# ESP.net
KiCad netlist of a schematic drawn in EAGLE
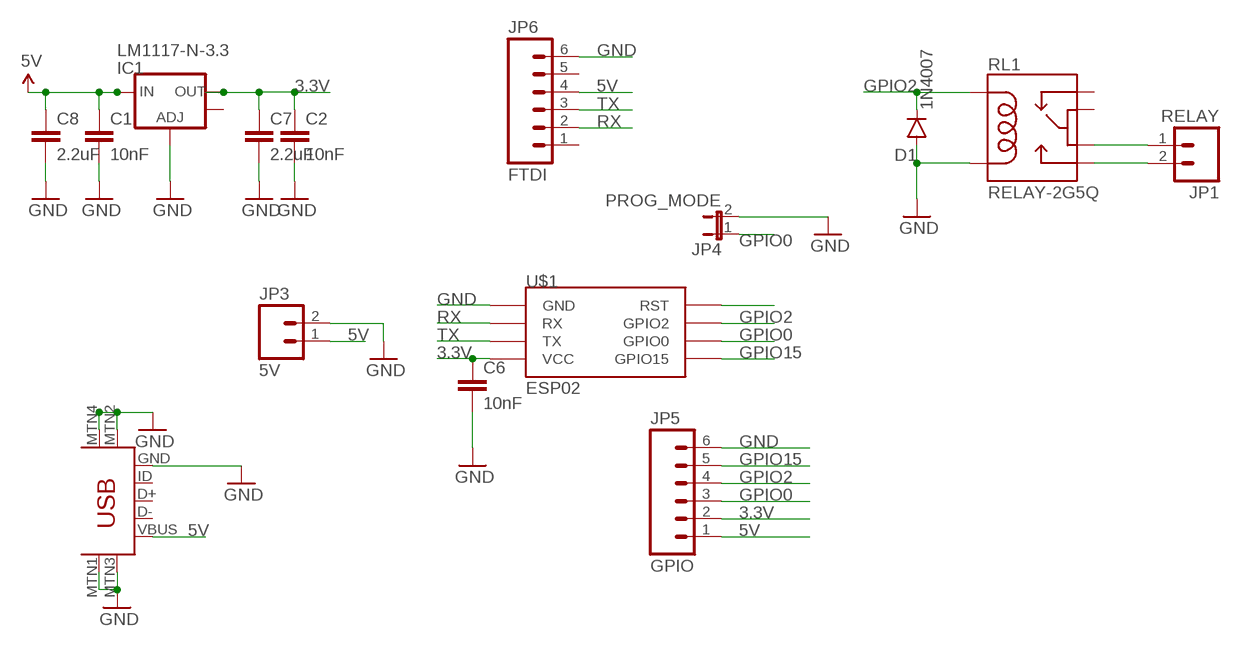
[diagram p0: schematic, sheet 1]

(export (version "E")
  (design (tool "Eeschema 10.0.6"))
  (components
    (comp (ref "C1")
      (value "10nF")
      (footprint "eagle-import:0603-CAP")
      (libsource (lib "eagle-import") (part "10NF/10000PF-50V-10%(0603)"))
    )
    (comp (ref "C2")
      (value "10nF")
      (footprint "eagle-import:0603-CAP")
      (libsource (lib "eagle-import") (part "10NF/10000PF-50V-10%(0603)"))
    )
    (comp (ref "C6")
      (value "10nF")
      (footprint "eagle-import:0603-CAP")
      (libsource (lib "eagle-import") (part "10NF/10000PF-50V-10%(0603)"))
    )
    (comp (ref "C7")
      (value "2.2uF")
      (footprint "eagle-import:0805")
      (libsource (lib "eagle-import") (part "2.2UF-25V-+80/-20(0805)"))
    )
    (comp (ref "C8")
      (value "2.2uF")
      (footprint "eagle-import:0805")
      (libsource (lib "eagle-import") (part "2.2UF-25V-+80/-20(0805)"))
    )
    (comp (ref "D1")
      (value "1N4007")
      (footprint "eagle-import:SMB-DIODE")
      (libsource (lib "eagle-import") (part "DIODESMB"))
    )
    (comp (ref "IC1")
      (value "LM1117-N-3.3")
      (footprint "eagle-import:SOT223")
      (libsource (lib "eagle-import") (part "V_REG_LM1117SOT223"))
    )
    (comp (ref "JP1")
      (value "RELAY")
      (footprint "eagle-import:SCREWTERMINAL-5MM-2")
      (libsource (lib "eagle-import") (part "M025MM"))
    )
    (comp (ref "JP3")
      (value "5V")
      (footprint "eagle-import:SCREWTERMINAL-5MM-2")
      (libsource (lib "eagle-import") (part "M025MM"))
    )
    (comp (ref "JP4")
      (value "PROG_MODE")
      (footprint "eagle-import:1X02")
      (libsource (lib "eagle-import") (part "JUMPER-2PTH"))
    )
    (comp (ref "JP5")
      (value "GPIO")
      (footprint "eagle-import:1X06")
      (libsource (lib "eagle-import") (part "M06SILK_FEMALE_PTH"))
    )
    (comp (ref "JP6")
      (value "FTDI")
      (footprint "eagle-import:1X06")
      (libsource (lib "eagle-import") (part "M06SILK_FEMALE_PTH"))
    )
    (comp (ref "RL1")
      (value "RELAY-2G5Q")
      (footprint "eagle-import:RELAY-G5V")
      (libsource (lib "eagle-import") (part "RELAY-2G5Q"))
    )
    (comp (ref "U$1")
      (value "ESP02")
      (footprint "eagle-import:ESP02")
      (libsource (lib "eagle-import") (part "ESP02"))
    )
    (comp (ref "U$2")
      (value "USB")
      (footprint "eagle-import:USB-MINIB")
      (libsource (lib "eagle-import") (part "USB-MINIB-5PIN"))
    )
  )
  (nets
    (net (code "1") (name "/3.3V") (class "Default")
      (node (ref "C2") (pin "1") (pinfunction "1_1") (pintype "passive"))
      (node (ref "C6") (pin "1") (pinfunction "1_1") (pintype "passive"))
      (node (ref "C7") (pin "1") (pinfunction "1_1") (pintype "passive"))
      (node (ref "IC1") (pin "2") (pinfunction "OUT_2") (pintype "output"))
      (node (ref "JP5") (pin "2") (pinfunction "2_2") (pintype "passive"))
      (node (ref "U$1") (pin "VCC") (pinfunction "VCC_VCC") (pintype "bidirectional"))
    )
    (net (code "2") (name "/GPIO0") (class "Default")
      (node (ref "JP4") (pin "1") (pinfunction "1_1") (pintype "passive"))
      (node (ref "JP5") (pin "3") (pinfunction "3_3") (pintype "passive"))
      (node (ref "U$1") (pin "GPIO0") (pinfunction "GPIO0_GPIO0") (pintype "bidirectional"))
    )
    (net (code "3") (name "/GPIO2") (class "Default")
      (node (ref "D1") (pin "C") (pinfunction "C_C") (pintype "passive"))
      (node (ref "JP5") (pin "4") (pinfunction "4_4") (pintype "passive"))
      (node (ref "RL1") (pin "2") (pinfunction "2_2") (pintype "bidirectional"))
      (node (ref "U$1") (pin "GPIO2") (pinfunction "GPIO2_GPIO2") (pintype "bidirectional"))
    )
    (net (code "4") (name "/GPIO15") (class "Default")
      (node (ref "JP5") (pin "5") (pinfunction "5_5") (pintype "passive"))
      (node (ref "U$1") (pin "GPIO15/POWERDOWN") (pinfunction "GPIO15_GPIO15/POWERDOWN") (pintype "bidirectional"))
    )
    (net (code "5") (name "/RX") (class "Default")
      (node (ref "JP6") (pin "2") (pinfunction "2_2") (pintype "passive"))
      (node (ref "U$1") (pin "RX") (pinfunction "RX_RX") (pintype "bidirectional"))
    )
    (net (code "6") (name "/TX") (class "Default")
      (node (ref "JP6") (pin "3") (pinfunction "3_3") (pintype "passive"))
      (node (ref "U$1") (pin "TX") (pinfunction "TX_TX") (pintype "bidirectional"))
    )
    (net (code "7") (name "5V") (class "Default")
      (node (ref "C1") (pin "1") (pinfunction "1_1") (pintype "passive"))
      (node (ref "C8") (pin "1") (pinfunction "1_1") (pintype "passive"))
      (node (ref "IC1") (pin "3") (pinfunction "IN_3") (pintype "input"))
      (node (ref "JP3") (pin "1") (pinfunction "1_1") (pintype "passive"))
      (node (ref "JP5") (pin "1") (pinfunction "1_1") (pintype "passive"))
      (node (ref "JP6") (pin "4") (pinfunction "4_4") (pintype "passive"))
      (node (ref "U$2") (pin "VBUS") (pinfunction "VBUS_VBUS") (pintype "bidirectional"))
    )
    (net (code "8") (name "GND") (class "Default")
      (node (ref "C1") (pin "2") (pinfunction "2_2") (pintype "passive"))
      (node (ref "C2") (pin "2") (pinfunction "2_2") (pintype "passive"))
      (node (ref "C6") (pin "2") (pinfunction "2_2") (pintype "passive"))
      (node (ref "C7") (pin "2") (pinfunction "2_2") (pintype "passive"))
      (node (ref "C8") (pin "2") (pinfunction "2_2") (pintype "passive"))
      (node (ref "D1") (pin "A") (pinfunction "A_A") (pintype "passive"))
      (node (ref "IC1") (pin "1") (pinfunction "ADJ_1") (pintype "input"))
      (node (ref "JP3") (pin "2") (pinfunction "2_2") (pintype "passive"))
      (node (ref "JP4") (pin "2") (pinfunction "2_2") (pintype "passive"))
      (node (ref "JP5") (pin "6") (pinfunction "6_6") (pintype "passive"))
      (node (ref "JP6") (pin "6") (pinfunction "6_6") (pintype "passive"))
      (node (ref "RL1") (pin "9") (pinfunction "9_9") (pintype "bidirectional"))
      (node (ref "U$1") (pin "GND") (pinfunction "GND_GND") (pintype "bidirectional"))
      (node (ref "U$2") (pin "GND") (pinfunction "GND_GND") (pintype "bidirectional"))
      (node (ref "U$2") (pin "MTN1") (pinfunction "MTN2_MTN1") (pintype "bidirectional"))
      (node (ref "U$2") (pin "MTN2") (pinfunction "MTN3_MTN2") (pintype "bidirectional"))
      (node (ref "U$2") (pin "MTN3") (pinfunction "MTN1_MTN3") (pintype "bidirectional"))
      (node (ref "U$2") (pin "MTN4") (pinfunction "MTN4_MTN4") (pintype "bidirectional"))
    )
    (net (code "9") (name "Net-(JP1-Pad1)") (class "Default")
      (node (ref "JP1") (pin "1") (pinfunction "1_1") (pintype "passive"))
      (node (ref "RL1") (pin "6") (pinfunction "6_6") (pintype "bidirectional"))
    )
    (net (code "10") (name "Net-(JP1-Pad2)") (class "Default")
      (node (ref "JP1") (pin "2") (pinfunction "2_2") (pintype "passive"))
      (node (ref "RL1") (pin "10") (pinfunction "10_10") (pintype "bidirectional"))
    )
    (net (code "11") (name "unconnected-(IC1-OUT-Pad4)") (class "Default")
      (node (ref "IC1") (pin "4") (pinfunction "OUT_4") (pintype "output"))
    )
    (net (code "12") (name "unconnected-(JP6-Pad1)") (class "Default")
      (node (ref "JP6") (pin "1") (pinfunction "1_1") (pintype "passive"))
    )
    (net (code "13") (name "unconnected-(JP6-Pad5)") (class "Default")
      (node (ref "JP6") (pin "5") (pinfunction "5_5") (pintype "passive"))
    )
    (net (code "14") (name "unconnected-(RL1-Pad1)") (class "Default")
      (node (ref "RL1") (pin "1") (pinfunction "1_1") (pintype "bidirectional"))
    )
    (net (code "15") (name "unconnected-(RL1-Pad5)") (class "Default")
      (node (ref "RL1") (pin "5") (pinfunction "5_5") (pintype "bidirectional"))
    )
    (net (code "16") (name "unconnected-(U$1-PadRST)") (class "Default")
      (node (ref "U$1") (pin "RST") (pinfunction "RST_RST") (pintype "bidirectional"))
    )
    (net (code "17") (name "unconnected-(U$2-PadD+)") (class "Default")
      (node (ref "U$2") (pin "D+") (pinfunction "D+_D+") (pintype "bidirectional"))
    )
    (net (code "18") (name "unconnected-(U$2-PadD-)") (class "Default")
      (node (ref "U$2") (pin "D-") (pinfunction "D-_D-") (pintype "bidirectional"))
    )
    (net (code "19") (name "unconnected-(U$2-PadID)") (class "Default")
      (node (ref "U$2") (pin "ID") (pinfunction "ID_ID") (pintype "bidirectional"))
    )
  )
)
